# Microcontroller.net
KiCad netlist of a schematic drawn in Altium Designer
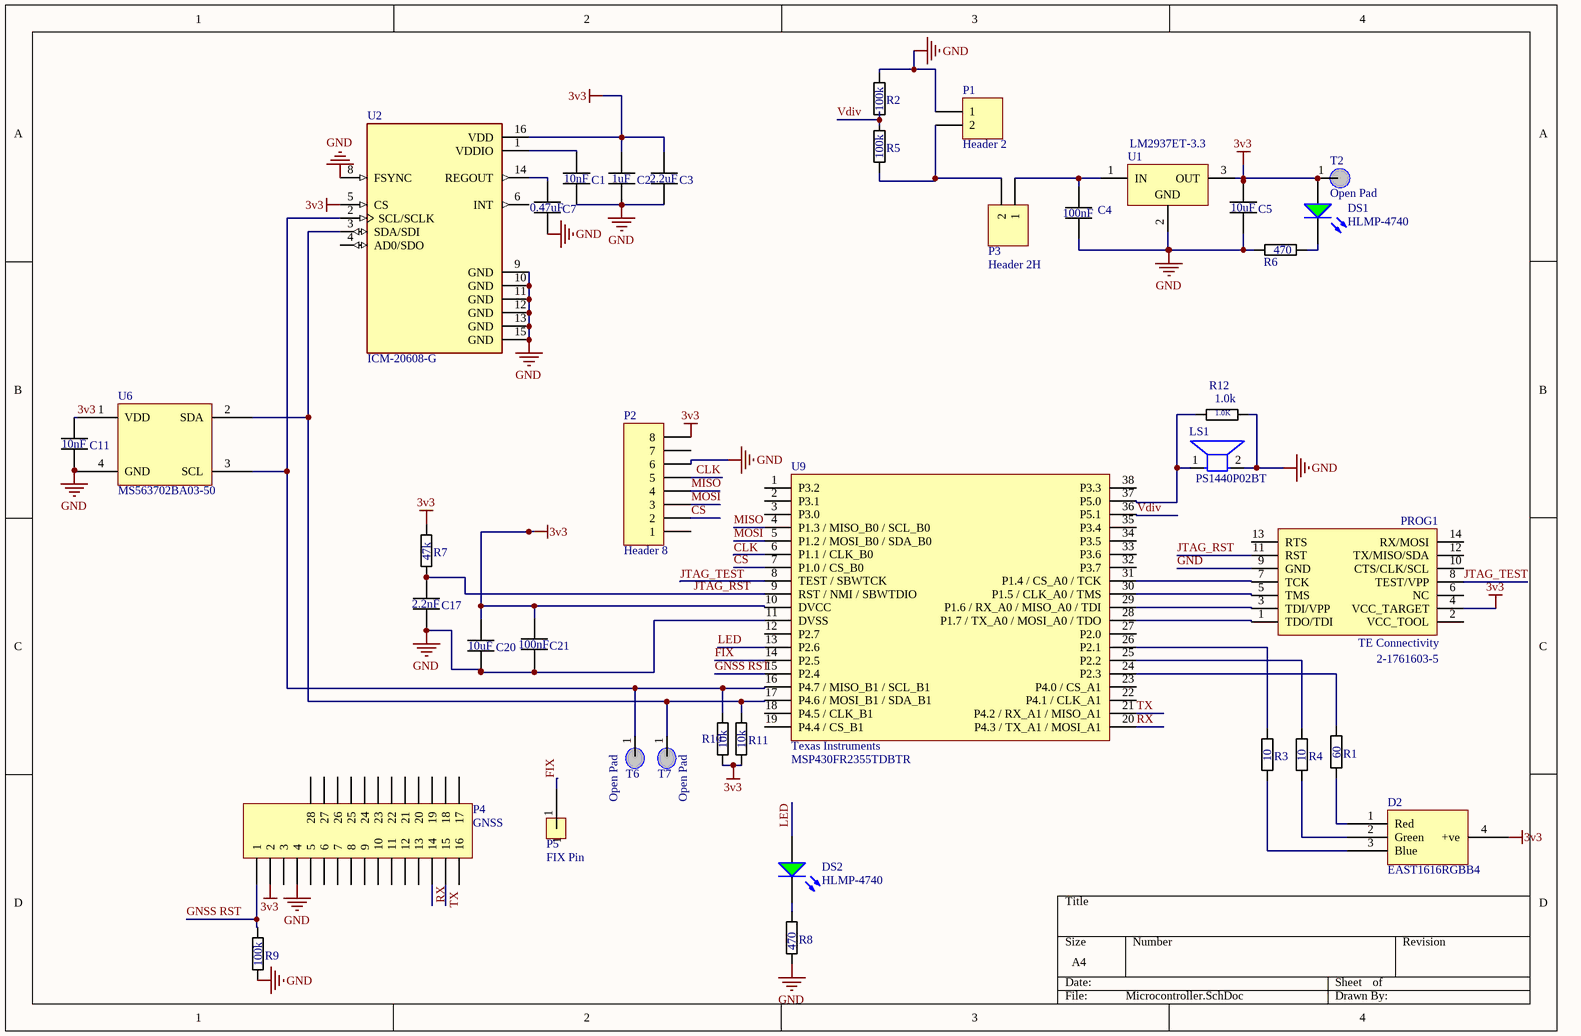
[diagram p0: Microcontroller.SchDoc]

(export (version "E")
  (design (tool "Eeschema 10.0.6"))
  (components
    (comp (ref "C1")
      (value "10nF")
      (footprint "0603 (Capacitor)")
      (description "Capacitor 10nF 0603 +/-5%")
      (fields
        (field (name "MANUFACTURER") "Murata")
        (field (name "MANUFACTURER PARTNO") "GRM1885C1H103JA01D")
      )
      (libsource (lib "Passives") (part "C-n-010.000-5-0603"))
    )
    (comp (ref "C2")
      (value "1uF")
      (footprint "0603 (Capacitor)")
      (description "Capacitor 1uF 0603 +/-5%")
      (fields
        (field (name "MANUFACTURER") "Murata")
        (field (name "MANUFACTURER PARTNO") "GCM1885C2A102JA16D")
      )
      (libsource (lib "Passives") (part "C-n-001.000-5-0603"))
    )
    (comp (ref "C3")
      (value "2.2uF")
      (footprint "0603 (Capacitor)")
      (description "Capacitor 2,2uF 0603 +/-5%")
      (fields
        (field (name "MANUFACTURER") "Murata")
        (field (name "MANUFACTURER PARTNO") "GCM1885C2A102JA16D")
      )
      (libsource (lib "Passives") (part "C-n-001.000-5-0603"))
    )
    (comp (ref "C4")
      (value "100nF")
      (footprint "0603 (Capacitor)")
      (description "Capacitor 100nF 0603 +/-10%")
      (fields
        (field (name "MANUFACTURER") "Murata")
        (field (name "MANUFACTURER PARTNO") "GRM188R72A104KA35D")
      )
      (libsource (lib "Passives") (part "C-n-100.000-10-0603"))
    )
    (comp (ref "C5")
      (value "10uF")
      (footprint "0603 (Capacitor)")
      (description "Capacitor 10uF 0603 +/-10%")
      (fields
        (field (name "MANUFACTURER") "Murata")
        (field (name "MANUFACTURER PARTNO") "GRM188R72A104KA35D")
      )
      (libsource (lib "Passives") (part "C-n-100.000-10-0603"))
    )
    (comp (ref "C7")
      (value "0.47uF")
      (footprint "0603 (Capacitor)")
      (description "Capacitor 0.47uF 0603 +/-5%")
      (fields
        (field (name "MANUFACTURER") "Murata")
        (field (name "MANUFACTURER PARTNO") "GRM1885C1H103JA01D")
      )
      (libsource (lib "Passives") (part "C-n-010.000-5-0603"))
    )
    (comp (ref "C11")
      (value "10nF")
      (footprint "0603 (Capacitor)")
      (description "Capacitor 10nF 0603 +/-5%")
      (fields
        (field (name "MANUFACTURER") "Murata")
        (field (name "MANUFACTURER PARTNO") "GRM1885C1H103JA01D")
      )
      (libsource (lib "Passives") (part "C-n-010.000-5-0603"))
    )
    (comp (ref "C17")
      (value "2.2nF")
      (footprint "0603 (Capacitor)")
      (description "Capacitor 2.2nF 0603 +/-5%")
      (fields
        (field (name "MANUFACTURER") "Murata")
        (field (name "MANUFACTURER PARTNO") "GCM1885C2A102JA16D")
      )
      (libsource (lib "Passives") (part "C-n-001.000-5-0603"))
    )
    (comp (ref "C20")
      (value "10uF")
      (footprint "0603 (Capacitor)")
      (description "Capacitor 10uF 0603 +/-5%")
      (fields
        (field (name "MANUFACTURER") "Murata")
        (field (name "MANUFACTURER PARTNO") "GCM1885C2A102JA16D")
      )
      (libsource (lib "Passives") (part "C-n-001.000-5-0603"))
    )
    (comp (ref "C21")
      (value "100nF")
      (footprint "0603 (Capacitor)")
      (description "Capacitor 100nF 0603 +/-10%")
      (fields
        (field (name "MANUFACTURER") "Murata")
        (field (name "MANUFACTURER PARTNO") "GRM188R72A104KA35D")
      )
      (libsource (lib "Passives") (part "C-n-100.000-10-0603"))
    )
    (comp (ref "D2")
      (value "EAST1616RGBB4")
      (footprint "EAST1616RGBB4 - duplicate1")
      (libsource (lib "Schlib") (part "EAST1616RGBB4"))
    )
    (comp (ref "DS1")
      (value "HLMP-4740")
      (footprint "AVAG-HLMP-4740")
      (description "T-1 3/4 (5 mm) Low Current LED Lamp, Green, 1.9 V, -20 to 100 degC, 2-Pin THD, RoHS, Bulk")
      (fields (field (name "MANUFACTURER") "AvagoTechnologies"))
      (libsource (lib "Schlib") (part "CMP-2000-06413-1"))
    )
    (comp (ref "DS2")
      (value "HLMP-4740")
      (footprint "AVAG-HLMP-4740")
      (description "T-1 3/4 (5 mm) Low Current LED Lamp, Green, 1.9 V, -20 to 100 degC, 2-Pin THD, RoHS, Bulk")
      (fields (field (name "MANUFACTURER") "AvagoTechnologies"))
      (libsource (lib "Schlib") (part "CMP-2000-06413-1"))
    )
    (comp (ref "LS1")
      (value "PS1440P02BT")
      (footprint "BUZZER_PS1440P02BT")
      (description "Buzzers Transducer, Externally Driven Piezo 3V 4kHz 75dB @ 3V, 10cm Through Hole PC Pins")
      (fields (field (name "MF") "TDK") (field (name "DIGI-KEY_PART_NUMBER") "445-5242-1-ND"))
      (libsource (lib "Schlib") (part "PS1440P02BT"))
    )
    (comp (ref "P1")
      (value "Header 2")
      (footprint "Battery Connector- 620102131822")
      (description "Header, 2-Pin")
      (fields (field (name "PUBLISHER") "Altium Limited"))
      (libsource (lib "Miscellaneous Connectors") (part "Header 2"))
    )
    (comp (ref "P2")
      (value "Header 8")
      (footprint "HDR1X8")
      (description "Header, 8-Pin")
      (fields (field (name "PUBLISHER") "Altium Limited"))
      (libsource (lib "Miscellaneous Connectors") (part "Header 8"))
    )
    (comp (ref "P3")
      (value "Header 2H")
      (footprint "HDR1X2H")
      (description "Header, 2-Pin, Right Angle")
      (fields (field (name "PUBLISHER") "Altium Limited"))
      (libsource (lib "Miscellaneous Connectors") (part "Header 2H"))
    )
    (comp (ref "P4")
      (value "GNSS")
      (footprint "HDR2X16_CEN")
      (description "Header, 16-Pin, Dual row")
      (fields (field (name "PUBLISHER") "Altium Limited"))
      (libsource (lib "Miscellaneous Connectors") (part "Header 16X2A"))
    )
    (comp (ref "P5")
      (value "FIX Pin")
      (footprint "Header 1 Pin")
      (libsource (lib "Schlib") (part "Head 1-pin"))
    )
    (comp (ref "PROG1")
      (value "MSP430 Programming Header")
      (footprint "TE 2-1761603-5")
      (description "14 Pin JTAG Header for MSP430 Debug Probe")
      (fields
        (field (name "MANUFACTURER") "TE Connectivity")
        (field (name "MANUFUCTURER PARTNO") "2-1761603-5")
      )
      (libsource (lib "Ti MSP430") (part "MSP430 Programming Header"))
    )
    (comp (ref "R1")
      (value "60")
      (footprint "0603 (Resistor)")
      (description "Resistor 60 0603 +/-1%")
      (fields
        (field (name "MANUFACTURER") "Vishay Dale")
        (field (name "MANUFACTURER PARTNO") "CRCW060310K0FKEAHP")
      )
      (libsource (lib "Passives") (part "R-k-010.000-1-0603"))
    )
    (comp (ref "R2")
      (value "100k")
      (footprint "0603 (Resistor)")
      (description "Resistor 100k 0603 +/-1%")
      (fields
        (field (name "MANUFACTURER") "Vishay Dale")
        (field (name "MANUFACTURER PARTNO") "CRCW0603100KFKEAHP")
      )
      (libsource (lib "Passives") (part "R-k-100.000-1-0603"))
    )
    (comp (ref "R3")
      (value "10")
      (footprint "0603 (Resistor)")
      (description "Resistor 10 0603 +/-1%")
      (fields
        (field (name "MANUFACTURER") "Vishay Dale")
        (field (name "MANUFACTURER PARTNO") "CRCW060310K0FKEAHP")
      )
      (libsource (lib "Passives") (part "R-k-010.000-1-0603"))
    )
    (comp (ref "R4")
      (value "10")
      (footprint "0603 (Resistor)")
      (description "Resistor 10 0603 +/-1%")
      (fields
        (field (name "MANUFACTURER") "Vishay Dale")
        (field (name "MANUFACTURER PARTNO") "CRCW060310K0FKEAHP")
      )
      (libsource (lib "Passives") (part "R-k-010.000-1-0603"))
    )
    (comp (ref "R5")
      (value "100k")
      (footprint "0603 (Resistor)")
      (description "Resistor 100k 0603 +/-1%")
      (fields
        (field (name "MANUFACTURER") "Vishay Dale")
        (field (name "MANUFACTURER PARTNO") "CRCW0603100KFKEAHP")
      )
      (libsource (lib "Passives") (part "R-k-100.000-1-0603"))
    )
    (comp (ref "R6")
      (value "470")
      (footprint "0603 (Resistor)")
      (description "Resistor 1.5k 0603 +/-1%")
      (fields
        (field (name "MANUFACTURER") "Vishay Dale")
        (field (name "MANUFACTURER PARTNO") "CRCW06031K50FKEAHP")
      )
      (libsource (lib "Passives") (part "R-k-001.500-1-0603"))
    )
    (comp (ref "R7")
      (value "47k")
      (footprint "0603 (Resistor)")
      (description "Resistor 47k 0603 +/-1%")
      (fields
        (field (name "MANUFACTURER") "Vishay Dale")
        (field (name "MANUFACTURER PARTNO") "CRCW060368K0FKEAHP")
      )
      (libsource (lib "Passives") (part "R-k-068.000-1-0603"))
    )
    (comp (ref "R8")
      (value "470")
      (footprint "0603 (Resistor)")
      (description "Resistor 1.5k 0603 +/-1%")
      (fields
        (field (name "MANUFACTURER") "Vishay Dale")
        (field (name "MANUFACTURER PARTNO") "CRCW06031K50FKEAHP")
      )
      (libsource (lib "Passives") (part "R-k-001.500-1-0603"))
    )
    (comp (ref "R9")
      (value "100k")
      (footprint "0603 (Resistor)")
      (description "Resistor 100k 0603 +/-1%")
      (fields
        (field (name "MANUFACTURER") "Vishay Dale")
        (field (name "MANUFACTURER PARTNO") "CRCW0603100KFKEAHP")
      )
      (libsource (lib "Passives") (part "R-k-100.000-1-0603"))
    )
    (comp (ref "R10")
      (value "10k")
      (footprint "0603 (Resistor)")
      (description "Resistor 10k 0603 +/-1%")
      (fields
        (field (name "MANUFACTURER") "Vishay Dale")
        (field (name "MANUFACTURER PARTNO") "CRCW060310K0FKEAHP")
      )
      (libsource (lib "Passives") (part "R-k-010.000-1-0603"))
    )
    (comp (ref "R11")
      (value "10k")
      (footprint "0603 (Resistor)")
      (description "Resistor 10k 0603 +/-1%")
      (fields
        (field (name "MANUFACTURER") "Vishay Dale")
        (field (name "MANUFACTURER PARTNO") "CRCW060310K0FKEAHP")
      )
      (libsource (lib "Passives") (part "R-k-010.000-1-0603"))
    )
    (comp (ref "R12")
      (value "1.0k")
      (footprint "1.0k through hole")
      (libsource (lib "Schlib") (part "1.0k through hole resistor"))
    )
    (comp (ref "T2") (value "Open Pad") (footprint "Open Pad") (libsource (lib "Schlib") (part "Open Pad")))
    (comp (ref "T6") (value "Open Pad") (footprint "Open Pad") (libsource (lib "Schlib") (part "Open Pad")))
    (comp (ref "T7") (value "Open Pad") (footprint "Open Pad") (libsource (lib "Schlib") (part "Open Pad")))
    (comp (ref "U1")
      (value "LM2937ET-3.3")
      (footprint "NDE0003A")
      (description "500 mA Low Dropout Regulator, 3-pin TO-220")
      (fields (field (name "MANUFACTURER") "Texas Instruments"))
      (libsource (lib "Voltage Regulator") (part "CMP-0062-02522-3"))
    )
    (comp (ref "U2")
      (value "ICM-20608-G")
      (footprint "ICM-20608-G")
      (description "Accelerometer, Gyroscope, 6 Axis Sensor IÂ²C, SPI Output")
      (fields (field (name "MF") "TDK InvenSense"))
      (libsource (lib "ICM-20608-G") (part "ICM-20608-G"))
    )
    (comp (ref "U6")
      (value "MS563702BA03-50")
      (footprint "MS5837-30BA")
      (description "Pressure Sensor, Absolute, 2Bar, I2C")
      (fields
        (field (name "MANUFACTURER") "TE Connectivity")
        (field (name "MANUFACTURER PART NUMBER") "MS5837-02BA21")
      )
      (libsource (lib "Schlib") (part "MS5837-02BA21"))
    )
    (comp (ref "U9")
      (value "MSP430FR2355 38-TFSOP")
      (footprint "MSP430FR2355 38-TFSOP")
      (description "MSP430 Microcontroller")
      (fields
        (field (name "MANUFACTURER") "Texas Instruments")
        (field (name "MANUFACTURER PART NUMBER") "MSP430FR2355TDBTR")
      )
      (libsource (lib "Ti MSP430") (part "MSP430FR2355 38-TFSOP"))
    )
  )
  (nets
    (net (code "2") (name "/CLK") (class "Default")
      (node (ref "P2") (pin "5") (pinfunction "5_5") (pintype "passive"))
      (node (ref "U9") (pin "6") (pinfunction "P1.1_/_CLK_B0_6") (pintype "passive"))
    )
    (net (code "3") (name "/CS") (class "Default")
      (node (ref "P2") (pin "2") (pinfunction "2_2") (pintype "passive"))
      (node (ref "U9") (pin "7") (pinfunction "P1.0_/_CS_B0_7") (pintype "passive"))
    )
    (net (code "4") (name "/FIX") (class "Default")
      (node (ref "P5") (pin "1") (pinfunction "1_1") (pintype "passive"))
      (node (ref "U9") (pin "14") (pinfunction "P2.5_14") (pintype "passive"))
    )
    (net (code "5") (name "/GNSS RST") (class "Default")
      (node (ref "P4") (pin "1") (pinfunction "1_1") (pintype "passive"))
      (node (ref "R9") (pin "1") (pinfunction "1_1") (pintype "passive"))
      (node (ref "U9") (pin "15") (pinfunction "P2.4_15") (pintype "passive"))
    )
    (net (code "6") (name "/JTAG_RST") (class "Default")
      (node (ref "C17") (pin "1") (pinfunction "1_1") (pintype "passive"))
      (node (ref "PROG1") (pin "11") (pinfunction "RST_11") (pintype "passive"))
      (node (ref "R7") (pin "2") (pinfunction "2_2") (pintype "passive"))
      (node (ref "U9") (pin "9") (pinfunction "RST_/_NMI_/_SBWTDIO_9") (pintype "passive"))
    )
    (net (code "7") (name "/JTAG_TEST") (class "Default")
      (node (ref "PROG1") (pin "8") (pinfunction "TEST/VPP_8") (pintype "passive"))
      (node (ref "U9") (pin "8") (pinfunction "TEST_/_SBWTCK_8") (pintype "passive"))
    )
    (net (code "8") (name "/LED") (class "Default")
      (node (ref "DS2") (pin "1") (pinfunction "A_1") (pintype "passive"))
      (node (ref "U9") (pin "13") (pinfunction "P2.6_13") (pintype "passive"))
    )
    (net (code "9") (name "/MISO") (class "Default")
      (node (ref "P2") (pin "4") (pinfunction "4_4") (pintype "passive"))
      (node (ref "U9") (pin "4") (pinfunction "P1.3_/_MISO_B0_/_SCL_B0_4") (pintype "passive"))
    )
    (net (code "10") (name "/MOSI") (class "Default")
      (node (ref "P2") (pin "3") (pinfunction "3_3") (pintype "passive"))
      (node (ref "U9") (pin "5") (pinfunction "P1.2_/_MOSI_B0_/_SDA_B0_5") (pintype "passive"))
    )
    (net (code "11") (name "/RX") (class "Default")
      (node (ref "P4") (pin "14") (pinfunction "14_14") (pintype "passive"))
      (node (ref "U9") (pin "20") (pinfunction "P4.3_/_TX_A1_/_MOSI_A1_20") (pintype "passive"))
    )
    (net (code "12") (name "/TX") (class "Default")
      (node (ref "P4") (pin "15") (pinfunction "15_15") (pintype "passive"))
      (node (ref "U9") (pin "21") (pinfunction "P4.2_/_RX_A1_/_MISO_A1_21") (pintype "passive"))
    )
    (net (code "13") (name "/Vdiv") (class "Default")
      (node (ref "R2") (pin "2") (pinfunction "2_2") (pintype "passive"))
      (node (ref "R5") (pin "1") (pinfunction "1_1") (pintype "passive"))
      (node (ref "U9") (pin "36") (pinfunction "P5.1_36") (pintype "passive"))
    )
    (net (code "14") (name "3v3") (class "Default")
      (node (ref "C11") (pin "1") (pinfunction "1_1") (pintype "passive"))
      (node (ref "C2") (pin "1") (pinfunction "1_1") (pintype "passive"))
      (node (ref "C20") (pin "1") (pinfunction "1_1") (pintype "passive"))
      (node (ref "C21") (pin "1") (pinfunction "1_1") (pintype "passive"))
      (node (ref "C3") (pin "1") (pinfunction "1_1") (pintype "passive"))
      (node (ref "C5") (pin "1") (pinfunction "1_1") (pintype "passive"))
      (node (ref "D2") (pin "4") (pinfunction "+ve_4") (pintype "passive"))
      (node (ref "DS1") (pin "1") (pinfunction "A_1") (pintype "passive"))
      (node (ref "P2") (pin "8") (pinfunction "8_8") (pintype "passive"))
      (node (ref "P4") (pin "2") (pinfunction "2_2") (pintype "passive"))
      (node (ref "PROG1") (pin "4") (pinfunction "VCC_TARGET_4") (pintype "passive"))
      (node (ref "R10") (pin "2") (pinfunction "2_2") (pintype "passive"))
      (node (ref "R11") (pin "2") (pinfunction "2_2") (pintype "passive"))
      (node (ref "R7") (pin "1") (pinfunction "1_1") (pintype "passive"))
      (node (ref "T2") (pin "1") (pintype "passive"))
      (node (ref "U1") (pin "3") (pinfunction "OUT_3") (pintype "power_in"))
      (node (ref "U2") (pin "16") (pinfunction "VDD_16") (pintype "power_in"))
      (node (ref "U2") (pin "5") (pinfunction "CS_5") (pintype "input"))
      (node (ref "U6") (pin "1") (pinfunction "VDD_1") (pintype "passive"))
      (node (ref "U9") (pin "10") (pinfunction "DVCC_10") (pintype "passive"))
    )
    (net (code "15") (name "GND") (class "Default")
      (node (ref "C1") (pin "2") (pinfunction "2_2") (pintype "passive"))
      (node (ref "C11") (pin "2") (pinfunction "2_2") (pintype "passive"))
      (node (ref "C17") (pin "2") (pinfunction "2_2") (pintype "passive"))
      (node (ref "C2") (pin "2") (pinfunction "2_2") (pintype "passive"))
      (node (ref "C20") (pin "2") (pinfunction "2_2") (pintype "passive"))
      (node (ref "C21") (pin "2") (pinfunction "2_2") (pintype "passive"))
      (node (ref "C3") (pin "2") (pinfunction "2_2") (pintype "passive"))
      (node (ref "C4") (pin "2") (pinfunction "2_2") (pintype "passive"))
      (node (ref "C5") (pin "2") (pinfunction "2_2") (pintype "passive"))
      (node (ref "C7") (pin "2") (pinfunction "2_2") (pintype "passive"))
      (node (ref "LS1") (pin "2") (pinfunction "2_2") (pintype "passive"))
      (node (ref "P1") (pin "1") (pinfunction "1_1") (pintype "passive"))
      (node (ref "P2") (pin "6") (pinfunction "6_6") (pintype "passive"))
      (node (ref "P4") (pin "4") (pinfunction "4_4") (pintype "passive"))
      (node (ref "PROG1") (pin "9") (pinfunction "GND_9") (pintype "passive"))
      (node (ref "R12") (pin "1") (pinfunction "1_1") (pintype "passive"))
      (node (ref "R2") (pin "1") (pinfunction "1_1") (pintype "passive"))
      (node (ref "R6") (pin "1") (pinfunction "1_1") (pintype "passive"))
      (node (ref "R8") (pin "2") (pinfunction "2_2") (pintype "passive"))
      (node (ref "R9") (pin "2") (pinfunction "2_2") (pintype "passive"))
      (node (ref "U1") (pin "2") (pinfunction "GND_2") (pintype "power_in"))
      (node (ref "U2") (pin "10") (pinfunction "GND_10") (pintype "power_in"))
      (node (ref "U2") (pin "11") (pinfunction "GND_11") (pintype "power_in"))
      (node (ref "U2") (pin "12") (pinfunction "GND_12") (pintype "power_in"))
      (node (ref "U2") (pin "13") (pinfunction "GND_13") (pintype "power_in"))
      (node (ref "U2") (pin "15") (pinfunction "GND_15") (pintype "power_in"))
      (node (ref "U2") (pin "8") (pinfunction "FSYNC_8") (pintype "input"))
      (node (ref "U2") (pin "9") (pinfunction "GND_9") (pintype "power_in"))
      (node (ref "U6") (pin "4") (pinfunction "GND_4") (pintype "passive"))
      (node (ref "U9") (pin "11") (pinfunction "DVSS_11") (pintype "passive"))
    )
    (net (code "16") (name "Net-(D2-Blue)") (class "Default")
      (node (ref "D2") (pin "3") (pinfunction "Blue_3") (pintype "passive"))
      (node (ref "R3") (pin "2") (pinfunction "2_2") (pintype "passive"))
    )
    (net (code "17") (name "Net-(D2-Green)") (class "Default")
      (node (ref "D2") (pin "2") (pinfunction "Green_2") (pintype "passive"))
      (node (ref "R4") (pin "2") (pinfunction "2_2") (pintype "passive"))
    )
    (net (code "18") (name "Net-(D2-Red)") (class "Default")
      (node (ref "D2") (pin "1") (pinfunction "Red_1") (pintype "passive"))
      (node (ref "R1") (pin "2") (pinfunction "2_2") (pintype "passive"))
    )
    (net (code "19") (name "Net-(DS1-K)") (class "Default")
      (node (ref "DS1") (pin "2") (pinfunction "K_2") (pintype "passive"))
      (node (ref "R6") (pin "2") (pinfunction "2_2") (pintype "passive"))
    )
    (net (code "20") (name "Net-(DS2-K)") (class "Default")
      (node (ref "DS2") (pin "2") (pinfunction "K_2") (pintype "passive"))
      (node (ref "R8") (pin "1") (pinfunction "1_1") (pintype "passive"))
    )
    (net (code "21") (name "Net-(P1-Pad2)") (class "Default")
      (node (ref "P1") (pin "2") (pinfunction "2_2") (pintype "passive"))
      (node (ref "P3") (pin "2") (pinfunction "2_2") (pintype "passive"))
      (node (ref "R5") (pin "2") (pinfunction "2_2") (pintype "passive"))
    )
    (net (code "22") (name "Net-(PROG1-TCK)") (class "Default")
      (node (ref "PROG1") (pin "7") (pinfunction "TCK_7") (pintype "passive"))
      (node (ref "U9") (pin "31") (pinfunction "P1.4_/_CS_A0_/_TCK_31") (pintype "passive"))
    )
    (net (code "23") (name "Net-(PROG1-TDI{slash}VPP)") (class "Default")
      (node (ref "PROG1") (pin "3") (pinfunction "TDI/VPP_3") (pintype "passive"))
      (node (ref "U9") (pin "29") (pinfunction "P1.6_/_RX_A0_/_MISO_A0_/_TDI_29") (pintype "passive"))
    )
    (net (code "24") (name "Net-(PROG1-TDO{slash}TDI)") (class "Default")
      (node (ref "PROG1") (pin "1") (pinfunction "TDO/TDI_1") (pintype "passive"))
      (node (ref "U9") (pin "28") (pinfunction "P1.7_/_TX_A0_/_MOSI_A0_/_TDO_28") (pintype "passive"))
    )
    (net (code "25") (name "Net-(PROG1-TMS)") (class "Default")
      (node (ref "PROG1") (pin "5") (pinfunction "TMS_5") (pintype "passive"))
      (node (ref "U9") (pin "30") (pinfunction "P1.5_/_CLK_A0_/_TMS_30") (pintype "passive"))
    )
    (net (code "26") (name "Net-(U1-IN)") (class "Default")
      (node (ref "C4") (pin "1") (pinfunction "1_1") (pintype "passive"))
      (node (ref "P3") (pin "1") (pinfunction "1_1") (pintype "passive"))
      (node (ref "U1") (pin "1") (pinfunction "IN_1") (pintype "power_in"))
    )
    (net (code "27") (name "Net-(U2-REGOUT)") (class "Default")
      (node (ref "C7") (pin "1") (pinfunction "1_1") (pintype "passive"))
      (node (ref "U2") (pin "14") (pinfunction "REGOUT_14") (pintype "output"))
    )
    (net (code "28") (name "Net-(U2-SCL{slash}SCLK)") (class "Default")
      (node (ref "R10") (pin "1") (pinfunction "1_1") (pintype "passive"))
      (node (ref "T6") (pin "1") (pintype "passive"))
      (node (ref "U2") (pin "2") (pinfunction "SCL/SCLK_2") (pintype "input"))
      (node (ref "U6") (pin "3") (pinfunction "SCL_3") (pintype "passive"))
      (node (ref "U9") (pin "16") (pinfunction "P4.7_/_MISO_B1_/_SCL_B1_16") (pintype "passive"))
    )
    (net (code "29") (name "Net-(U2-SDA{slash}SDI)") (class "Default")
      (node (ref "R11") (pin "1") (pinfunction "1_1") (pintype "passive"))
      (node (ref "T7") (pin "1") (pintype "passive"))
      (node (ref "U2") (pin "3") (pinfunction "SDA/SDI_3") (pintype "bidirectional"))
      (node (ref "U6") (pin "2") (pinfunction "SDA_2") (pintype "passive"))
      (node (ref "U9") (pin "17") (pinfunction "P4.6_/_MOSI_B1_/_SDA_B1_17") (pintype "passive"))
    )
    (net (code "30") (name "Net-(U2-VDDIO)") (class "Default")
      (node (ref "C1") (pin "1") (pinfunction "1_1") (pintype "passive"))
      (node (ref "U2") (pin "1") (pinfunction "VDDIO_1") (pintype "power_in"))
    )
    (net (code "31") (name "Net-(U9-P2.1)") (class "Default")
      (node (ref "R3") (pin "1") (pinfunction "1_1") (pintype "passive"))
      (node (ref "U9") (pin "26") (pinfunction "P2.1_26") (pintype "passive"))
    )
    (net (code "32") (name "Net-(U9-P2.2)") (class "Default")
      (node (ref "R4") (pin "1") (pinfunction "1_1") (pintype "passive"))
      (node (ref "U9") (pin "25") (pinfunction "P2.2_25") (pintype "passive"))
    )
    (net (code "33") (name "Net-(U9-P2.3)") (class "Default")
      (node (ref "R1") (pin "1") (pinfunction "1_1") (pintype "passive"))
      (node (ref "U9") (pin "24") (pinfunction "P2.3_24") (pintype "passive"))
    )
    (net (code "34") (name "Net-(U9-P5.0)") (class "Default")
      (node (ref "LS1") (pin "1") (pinfunction "1_1") (pintype "passive"))
      (node (ref "R12") (pin "2") (pinfunction "2_2") (pintype "passive"))
      (node (ref "U9") (pin "37") (pinfunction "P5.0_37") (pintype "passive"))
    )
    (net (code "35") (name "unconnected-(P2-Pad1)") (class "Default")
      (node (ref "P2") (pin "1") (pinfunction "1_1") (pintype "passive"))
    )
    (net (code "36") (name "unconnected-(P2-Pad7)") (class "Default")
      (node (ref "P2") (pin "7") (pinfunction "7_7") (pintype "passive"))
    )
    (net (code "37") (name "unconnected-(P4-17-Pad28)") (class "Default")
      (node (ref "P4") (pin "28") (pinfunction "17_28") (pintype "passive"))
    )
    (net (code "38") (name "unconnected-(P4-18-Pad27)") (class "Default")
      (node (ref "P4") (pin "27") (pinfunction "18_27") (pintype "passive"))
    )
    (net (code "39") (name "unconnected-(P4-19-Pad26)") (class "Default")
      (node (ref "P4") (pin "26") (pinfunction "19_26") (pintype "passive"))
    )
    (net (code "40") (name "unconnected-(P4-20-Pad25)") (class "Default")
      (node (ref "P4") (pin "25") (pinfunction "20_25") (pintype "passive"))
    )
    (net (code "41") (name "unconnected-(P4-21-Pad24)") (class "Default")
      (node (ref "P4") (pin "24") (pinfunction "21_24") (pintype "passive"))
    )
    (net (code "42") (name "unconnected-(P4-22-Pad23)") (class "Default")
      (node (ref "P4") (pin "23") (pinfunction "22_23") (pintype "passive"))
    )
    (net (code "43") (name "unconnected-(P4-23-Pad22)") (class "Default")
      (node (ref "P4") (pin "22") (pinfunction "23_22") (pintype "passive"))
    )
    (net (code "44") (name "unconnected-(P4-24-Pad21)") (class "Default")
      (node (ref "P4") (pin "21") (pinfunction "24_21") (pintype "passive"))
    )
    (net (code "45") (name "unconnected-(P4-25-Pad20)") (class "Default")
      (node (ref "P4") (pin "20") (pinfunction "25_20") (pintype "passive"))
    )
    (net (code "46") (name "unconnected-(P4-26-Pad19)") (class "Default")
      (node (ref "P4") (pin "19") (pinfunction "26_19") (pintype "passive"))
    )
    (net (code "47") (name "unconnected-(P4-27-Pad18)") (class "Default")
      (node (ref "P4") (pin "18") (pinfunction "27_18") (pintype "passive"))
    )
    (net (code "48") (name "unconnected-(P4-28-Pad17)") (class "Default")
      (node (ref "P4") (pin "17") (pinfunction "28_17") (pintype "passive"))
    )
    (net (code "49") (name "unconnected-(P4-Pad3)") (class "Default")
      (node (ref "P4") (pin "3") (pinfunction "3_3") (pintype "passive"))
    )
    (net (code "50") (name "unconnected-(P4-Pad5)") (class "Default")
      (node (ref "P4") (pin "5") (pinfunction "5_5") (pintype "passive"))
    )
    (net (code "51") (name "unconnected-(P4-Pad6)") (class "Default")
      (node (ref "P4") (pin "6") (pinfunction "6_6") (pintype "passive"))
    )
    (net (code "52") (name "unconnected-(P4-Pad7)") (class "Default")
      (node (ref "P4") (pin "7") (pinfunction "7_7") (pintype "passive"))
    )
    (net (code "53") (name "unconnected-(P4-Pad8)") (class "Default")
      (node (ref "P4") (pin "8") (pinfunction "8_8") (pintype "passive"))
    )
    (net (code "54") (name "unconnected-(P4-Pad9)") (class "Default")
      (node (ref "P4") (pin "9") (pinfunction "9_9") (pintype "passive"))
    )
    (net (code "55") (name "unconnected-(P4-Pad10)") (class "Default")
      (node (ref "P4") (pin "10") (pinfunction "10_10") (pintype "passive"))
    )
    (net (code "56") (name "unconnected-(P4-Pad11)") (class "Default")
      (node (ref "P4") (pin "11") (pinfunction "11_11") (pintype "passive"))
    )
    (net (code "57") (name "unconnected-(P4-Pad12)") (class "Default")
      (node (ref "P4") (pin "12") (pinfunction "12_12") (pintype "passive"))
    )
    (net (code "58") (name "unconnected-(P4-Pad13)") (class "Default")
      (node (ref "P4") (pin "13") (pinfunction "13_13") (pintype "passive"))
    )
    (net (code "59") (name "unconnected-(P4-Pad16)") (class "Default")
      (node (ref "P4") (pin "16") (pinfunction "16_16") (pintype "passive"))
    )
    (net (code "60") (name "unconnected-(PROG1-CTS{slash}CLK{slash}SCL-Pad10)") (class "Default")
      (node (ref "PROG1") (pin "10") (pinfunction "CTS/CLK/SCL_10") (pintype "passive"))
    )
    (net (code "61") (name "unconnected-(PROG1-NC-Pad6)") (class "Default")
      (node (ref "PROG1") (pin "6") (pinfunction "NC_6") (pintype "passive"))
    )
    (net (code "62") (name "unconnected-(PROG1-RTS-Pad13)") (class "Default")
      (node (ref "PROG1") (pin "13") (pinfunction "RTS_13") (pintype "passive"))
    )
    (net (code "63") (name "unconnected-(PROG1-RX{slash}MOSI-Pad14)") (class "Default")
      (node (ref "PROG1") (pin "14") (pinfunction "RX/MOSI_14") (pintype "passive"))
    )
    (net (code "64") (name "unconnected-(PROG1-TX{slash}MISO{slash}SDA-Pad12)") (class "Default")
      (node (ref "PROG1") (pin "12") (pinfunction "TX/MISO/SDA_12") (pintype "passive"))
    )
    (net (code "65") (name "unconnected-(PROG1-VCC_TOOL-Pad2)") (class "Default")
      (node (ref "PROG1") (pin "2") (pinfunction "VCC_TOOL_2") (pintype "passive"))
    )
    (net (code "66") (name "unconnected-(U2-AD0{slash}SDO-Pad4)") (class "Default")
      (node (ref "U2") (pin "4") (pinfunction "AD0/SDO_4") (pintype "bidirectional"))
    )
    (net (code "67") (name "unconnected-(U2-INT-Pad6)") (class "Default")
      (node (ref "U2") (pin "6") (pinfunction "INT_6") (pintype "output"))
    )
    (net (code "68") (name "unconnected-(U9-P2.0-Pad27)") (class "Default")
      (node (ref "U9") (pin "27") (pinfunction "P2.0_27") (pintype "passive"))
    )
    (net (code "69") (name "unconnected-(U9-P2.7-Pad12)") (class "Default")
      (node (ref "U9") (pin "12") (pinfunction "P2.7_12") (pintype "passive"))
    )
    (net (code "70") (name "unconnected-(U9-P3.0-Pad3)") (class "Default")
      (node (ref "U9") (pin "3") (pinfunction "P3.0_3") (pintype "passive"))
    )
    (net (code "71") (name "unconnected-(U9-P3.1-Pad2)") (class "Default")
      (node (ref "U9") (pin "2") (pinfunction "P3.1_2") (pintype "passive"))
    )
    (net (code "72") (name "unconnected-(U9-P3.2-Pad1)") (class "Default")
      (node (ref "U9") (pin "1") (pinfunction "P3.2_1") (pintype "passive"))
    )
    (net (code "73") (name "unconnected-(U9-P3.3-Pad38)") (class "Default")
      (node (ref "U9") (pin "38") (pinfunction "P3.3_38") (pintype "passive"))
    )
    (net (code "74") (name "unconnected-(U9-P3.4-Pad35)") (class "Default")
      (node (ref "U9") (pin "35") (pinfunction "P3.4_35") (pintype "passive"))
    )
    (net (code "75") (name "unconnected-(U9-P3.5-Pad34)") (class "Default")
      (node (ref "U9") (pin "34") (pinfunction "P3.5_34") (pintype "passive"))
    )
    (net (code "76") (name "unconnected-(U9-P3.6-Pad33)") (class "Default")
      (node (ref "U9") (pin "33") (pinfunction "P3.6_33") (pintype "passive"))
    )
    (net (code "77") (name "unconnected-(U9-P3.7-Pad32)") (class "Default")
      (node (ref "U9") (pin "32") (pinfunction "P3.7_32") (pintype "passive"))
    )
    (net (code "78") (name "unconnected-(U9-P4.0_{slash}_CS_A1-Pad23)") (class "Default")
      (node (ref "U9") (pin "23") (pinfunction "P4.0_/_CS_A1_23") (pintype "passive"))
    )
    (net (code "79") (name "unconnected-(U9-P4.1_{slash}_CLK_A1-Pad22)") (class "Default")
      (node (ref "U9") (pin "22") (pinfunction "P4.1_/_CLK_A1_22") (pintype "passive"))
    )
    (net (code "80") (name "unconnected-(U9-P4.4_{slash}_CS_B1-Pad19)") (class "Default")
      (node (ref "U9") (pin "19") (pinfunction "P4.4_/_CS_B1_19") (pintype "passive"))
    )
    (net (code "81") (name "unconnected-(U9-P4.5_{slash}_CLK_B1-Pad18)") (class "Default")
      (node (ref "U9") (pin "18") (pinfunction "P4.5_/_CLK_B1_18") (pintype "passive"))
    )
  )
)
